# Sheet2.net
KiCad netlist of a schematic drawn in Altium Designer
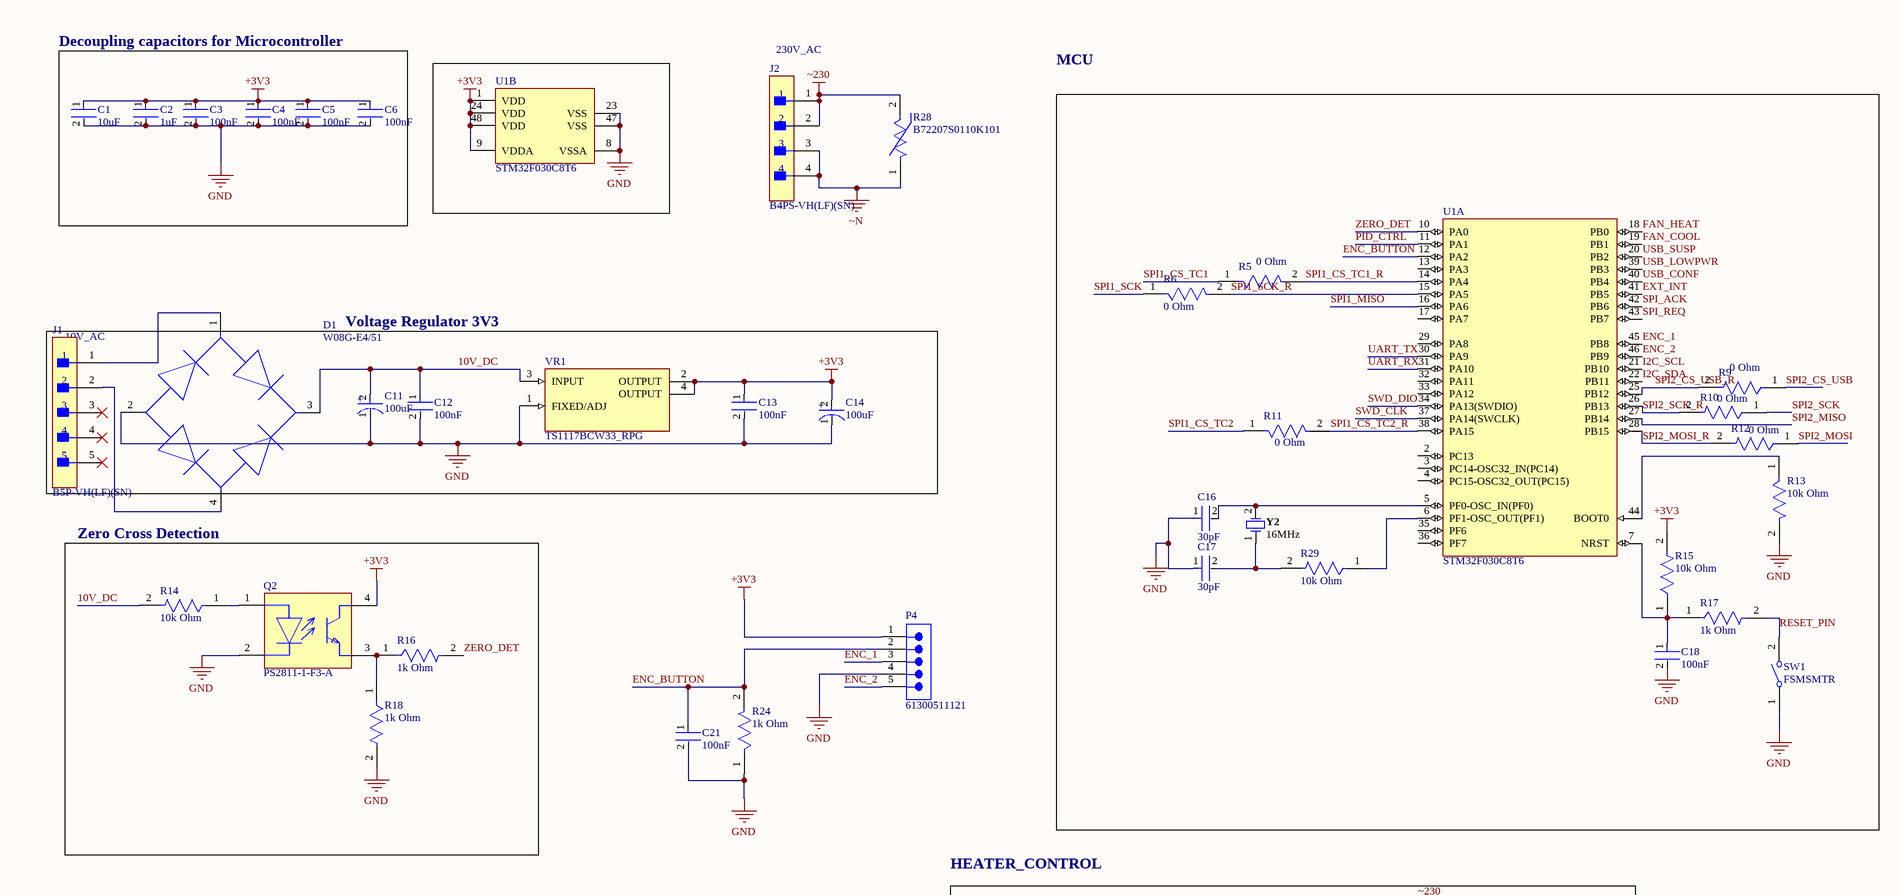
[diagram p0: Sheet2.SchDoc, top left]
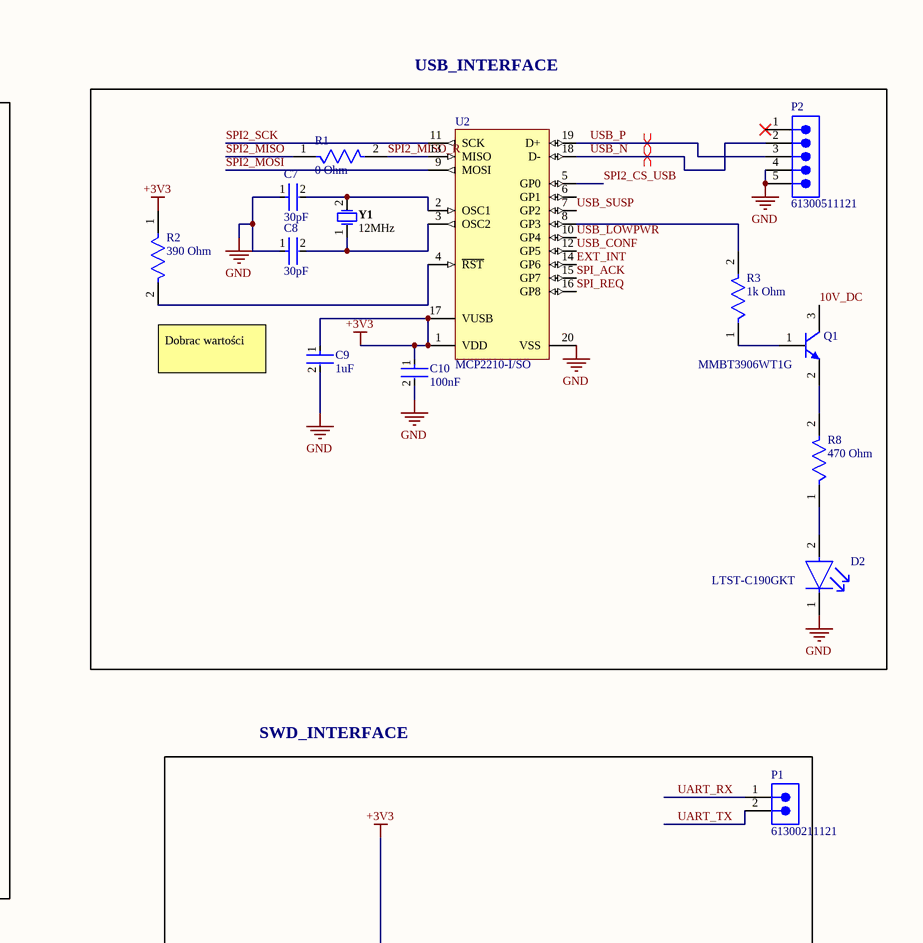
[diagram p1: Sheet2.SchDoc, top right]
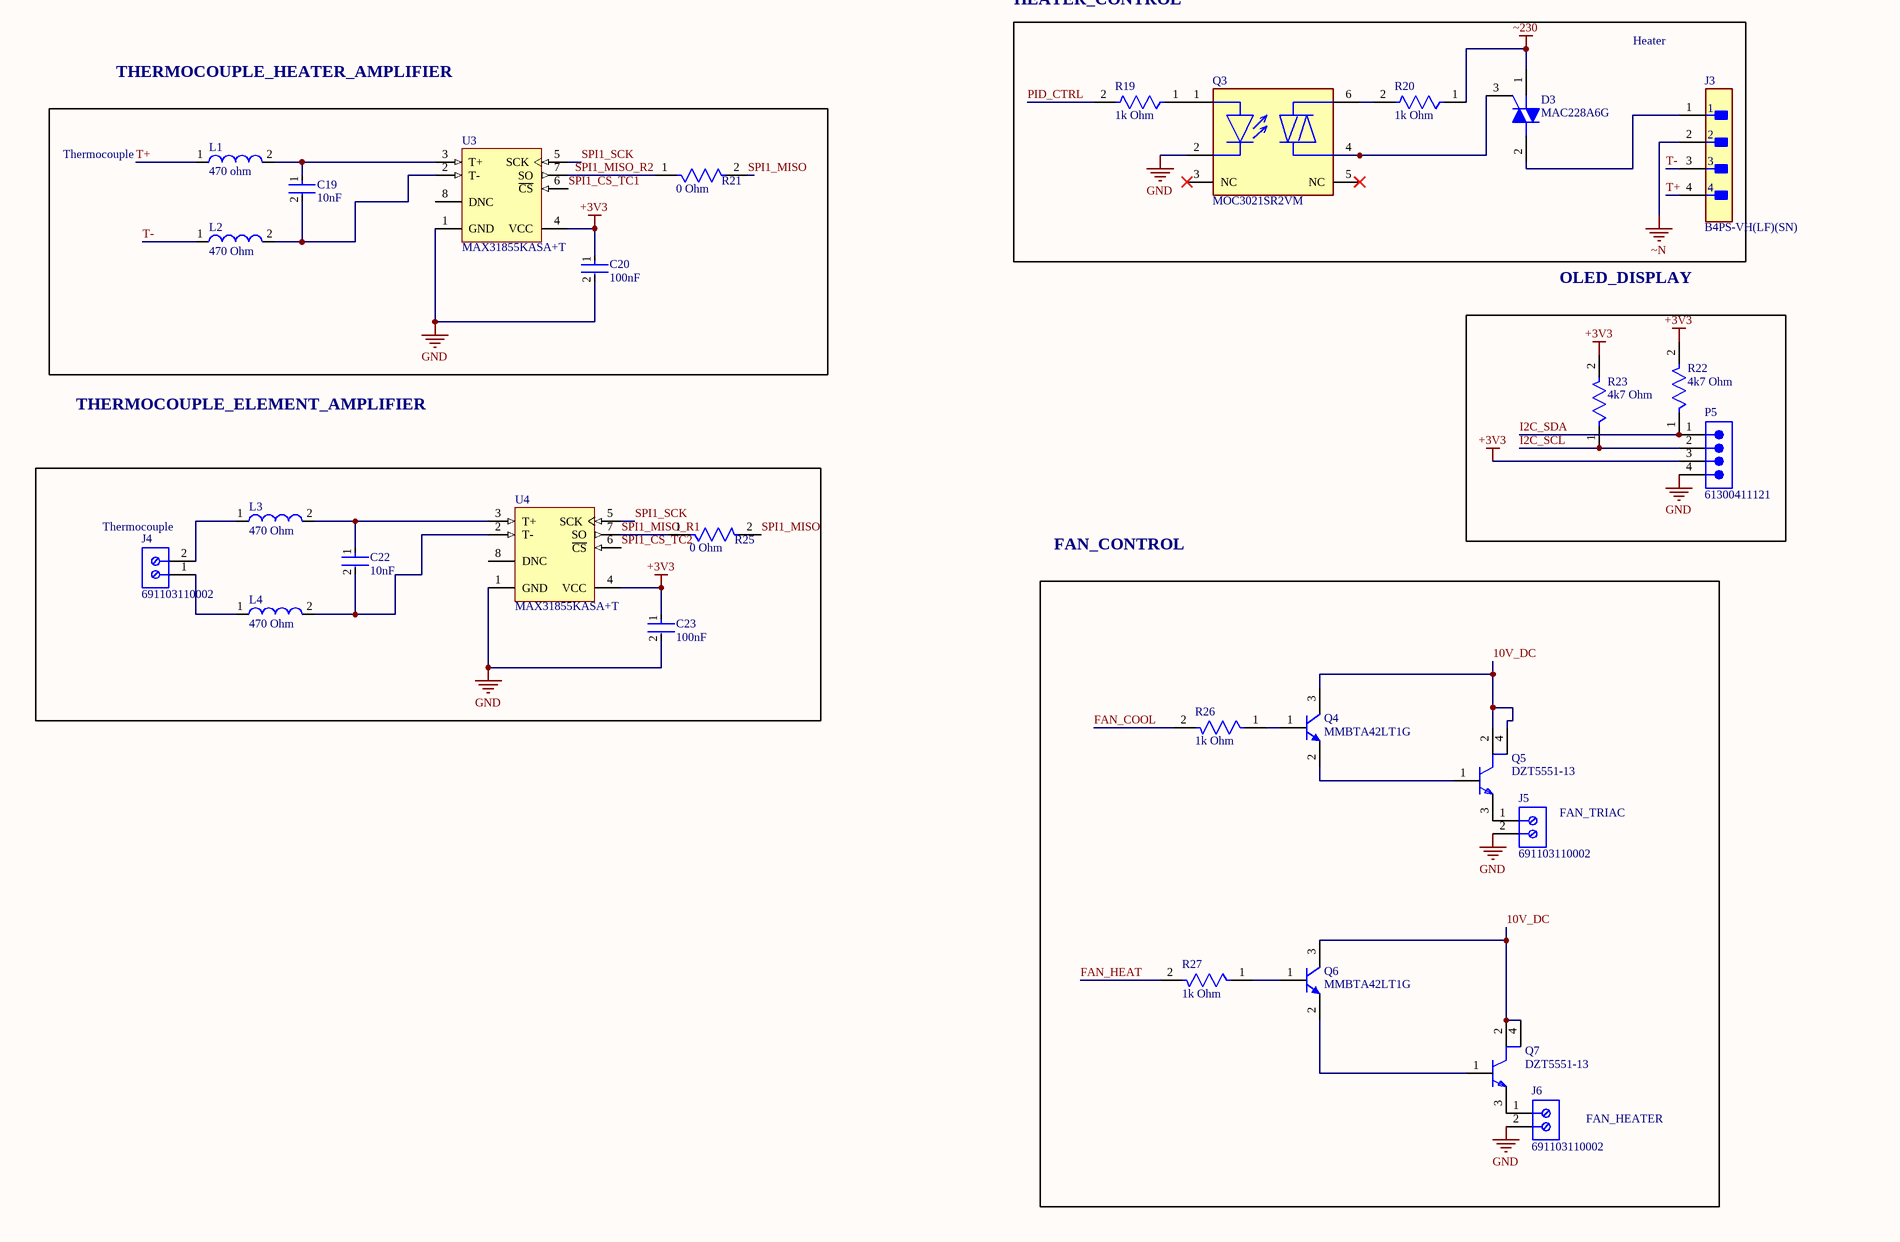
[diagram p2: Sheet2.SchDoc, bottom left]
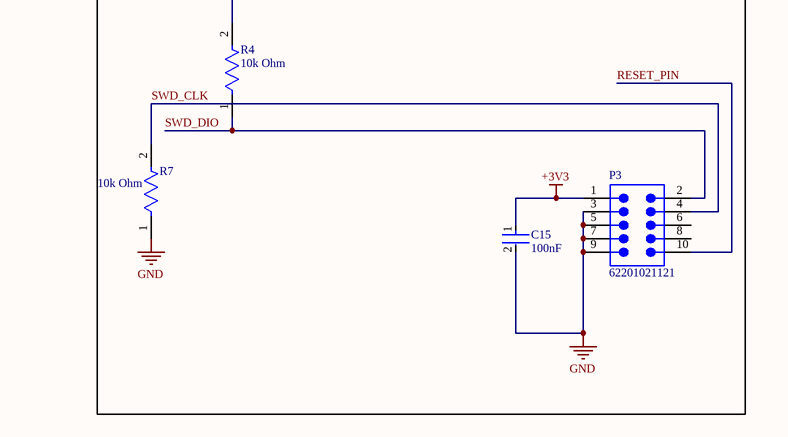
[diagram p3: Sheet2.SchDoc, bottom right]

(export (version "E")
  (design (tool "Eeschema 10.0.6"))
  (components
    (comp (ref "C1")
      (value "10uF")
      (footprint "FP-CC0805-0_85-MFG")
      (description "CAP CER 0.1UF 50V X7R 0805")
      (fields (field (name "TOLERANCE") "0.1") (field (name "MANUFACTURER PART NUMBER") "CC0805KRX7R9BB104"))
      (libsource (lib "Altium Content Vault") (part "11868f565c42a9108669ba33697ecf6"))
    )
    (comp (ref "C2")
      (value "1uF")
      (footprint "FP-CC0805-0_85-MFG")
      (description "CAP CER 0.1UF 50V X7R 0805")
      (fields (field (name "TOLERANCE") "0.1") (field (name "MANUFACTURER PART NUMBER") "CC0805KRX7R9BB104"))
      (libsource (lib "Altium Content Vault") (part "11868f565c42a9108669ba33697ecf6"))
    )
    (comp (ref "C3")
      (value "100nF")
      (footprint "FP-CC0805-0_85-MFG")
      (description "CAP CER 0.1UF 50V X7R 0805")
      (fields (field (name "TOLERANCE") "0.1") (field (name "MANUFACTURER PART NUMBER") "CC0805KRX7R9BB104"))
      (libsource (lib "Altium Content Vault") (part "11868f565c42a9108669ba33697ecf6"))
    )
    (comp (ref "C4")
      (value "100nF")
      (footprint "FP-CC0805-0_85-MFG")
      (description "CAP CER 0.1UF 50V X7R 0805")
      (fields (field (name "TOLERANCE") "0.1") (field (name "MANUFACTURER PART NUMBER") "CC0805KRX7R9BB104"))
      (libsource (lib "Altium Content Vault") (part "11868f565c42a9108669ba33697ecf6"))
    )
    (comp (ref "C5")
      (value "100nF")
      (footprint "FP-CC0805-0_85-MFG")
      (description "CAP CER 0.1UF 50V X7R 0805")
      (fields (field (name "TOLERANCE") "0.1") (field (name "MANUFACTURER PART NUMBER") "CC0805KRX7R9BB104"))
      (libsource (lib "Altium Content Vault") (part "11868f565c42a9108669ba33697ecf6"))
    )
    (comp (ref "C6")
      (value "100nF")
      (footprint "FP-CC0805-0_85-MFG")
      (description "CAP CER 0.1UF 50V X7R 0805")
      (fields (field (name "TOLERANCE") "0.1") (field (name "MANUFACTURER PART NUMBER") "CC0805KRX7R9BB104"))
      (libsource (lib "Altium Content Vault") (part "11868f565c42a9108669ba33697ecf6"))
    )
    (comp (ref "C7")
      (value "30pF")
      (footprint "FP-CC0805-0_85-MFG")
      (description "CAP CER 0.1UF 50V X7R 0805")
      (fields (field (name "TOLERANCE") "0.1") (field (name "MANUFACTURER PART NUMBER") "CC0805KRX7R9BB104"))
      (libsource (lib "Altium Content Vault") (part "11868f565c42a9108669ba33697ecf6"))
    )
    (comp (ref "C8")
      (value "30pF")
      (footprint "FP-CC0805-0_85-MFG")
      (description "CAP CER 0.1UF 50V X7R 0805")
      (fields (field (name "TOLERANCE") "0.1") (field (name "MANUFACTURER PART NUMBER") "CC0805KRX7R9BB104"))
      (libsource (lib "Altium Content Vault") (part "11868f565c42a9108669ba33697ecf6"))
    )
    (comp (ref "C9")
      (value "1uF")
      (footprint "FP-CC0805-0_85-MFG")
      (description "CAP CER 0.1UF 50V X7R 0805")
      (fields (field (name "TOLERANCE") "0.1") (field (name "MANUFACTURER PART NUMBER") "CC0805KRX7R9BB104"))
      (libsource (lib "Altium Content Vault") (part "11868f565c42a9108669ba33697ecf6"))
    )
    (comp (ref "C10")
      (value "100nF")
      (footprint "FP-CC0805-0_85-MFG")
      (description "CAP CER 0.1UF 50V X7R 0805")
      (fields (field (name "TOLERANCE") "0.1") (field (name "MANUFACTURER PART NUMBER") "CC0805KRX7R9BB104"))
      (libsource (lib "Altium Content Vault") (part "11868f565c42a9108669ba33697ecf6"))
    )
    (comp (ref "C11")
      (value "100uF")
      (footprint "FP-RAD-TH-D_10_0_5-L_12_5-MFG")
      (description "Aluminum Electrolytic Capacitors (Radial Lead Type) 3.3uF ±20% 400V")
      (fields (field (name "TOLERANCE") "20%") (field (name "VOLTAGE") "400V"))
      (libsource (lib "Altium Content Vault") (part "203bc49f2ac43e59fd269a8c329ed05"))
    )
    (comp (ref "C12")
      (value "100nF")
      (footprint "FP-CC0805-0_85-MFG")
      (description "CAP CER 0.1UF 50V X7R 0805")
      (fields (field (name "TOLERANCE") "0.1") (field (name "MANUFACTURER PART NUMBER") "CC0805KRX7R9BB104"))
      (libsource (lib "Altium Content Vault") (part "11868f565c42a9108669ba33697ecf6"))
    )
    (comp (ref "C13")
      (value "100nF")
      (footprint "FP-CC0805-0_85-MFG")
      (description "CAP CER 0.1UF 50V X7R 0805")
      (fields (field (name "TOLERANCE") "0.1") (field (name "MANUFACTURER PART NUMBER") "CC0805KRX7R9BB104"))
      (libsource (lib "Altium Content Vault") (part "11868f565c42a9108669ba33697ecf6"))
    )
    (comp (ref "C14")
      (value "100uF")
      (footprint "FP-RAD-TH-D_10_0_5-L_12_5-MFG")
      (description "Aluminum Electrolytic Capacitors (Radial Lead Type) 3.3uF ±20% 400V")
      (fields (field (name "TOLERANCE") "20%") (field (name "VOLTAGE") "400V"))
      (libsource (lib "Altium Content Vault") (part "203bc49f2ac43e59fd269a8c329ed05"))
    )
    (comp (ref "C15")
      (value "100nF")
      (footprint "FP-CC0805-0_85-MFG")
      (description "CAP CER 0.1UF 50V X7R 0805")
      (fields (field (name "TOLERANCE") "0.1") (field (name "MANUFACTURER PART NUMBER") "CC0805KRX7R9BB104"))
      (libsource (lib "Altium Content Vault") (part "11868f565c42a9108669ba33697ecf6"))
    )
    (comp (ref "C16")
      (value "30pF")
      (footprint "FP-CC0805-0_85-MFG")
      (description "CAP CER 0.1UF 50V X7R 0805")
      (fields (field (name "TOLERANCE") "0.1") (field (name "MANUFACTURER PART NUMBER") "CC0805KRX7R9BB104"))
      (libsource (lib "Altium Content Vault") (part "11868f565c42a9108669ba33697ecf6"))
    )
    (comp (ref "C17")
      (value "30pF")
      (footprint "FP-CC0805-0_85-MFG")
      (description "CAP CER 0.1UF 50V X7R 0805")
      (fields (field (name "TOLERANCE") "0.1") (field (name "MANUFACTURER PART NUMBER") "CC0805KRX7R9BB104"))
      (libsource (lib "Altium Content Vault") (part "11868f565c42a9108669ba33697ecf6"))
    )
    (comp (ref "C18")
      (value "100nF")
      (footprint "FP-CC0805-0_85-MFG")
      (description "CAP CER 0.1UF 50V X7R 0805")
      (fields (field (name "TOLERANCE") "0.1") (field (name "MANUFACTURER PART NUMBER") "CC0805KRX7R9BB104"))
      (libsource (lib "Altium Content Vault") (part "11868f565c42a9108669ba33697ecf6"))
    )
    (comp (ref "C19")
      (value "10nF")
      (footprint "FP-CC0805-0_85-MFG")
      (description "CAP CER 0.1UF 50V X7R 0805")
      (fields (field (name "TOLERANCE") "0.1") (field (name "MANUFACTURER PART NUMBER") "CC0805KRX7R9BB104"))
      (libsource (lib "Altium Content Vault") (part "11868f565c42a9108669ba33697ecf6"))
    )
    (comp (ref "C20")
      (value "100nF")
      (footprint "FP-CC0805-0_85-MFG")
      (description "CAP CER 0.1UF 50V X7R 0805")
      (fields (field (name "TOLERANCE") "0.1") (field (name "MANUFACTURER PART NUMBER") "CC0805KRX7R9BB104"))
      (libsource (lib "Altium Content Vault") (part "11868f565c42a9108669ba33697ecf6"))
    )
    (comp (ref "C21")
      (value "100nF")
      (footprint "FP-CC0805-0_85-MFG")
      (description "CAP CER 0.1UF 50V X7R 0805")
      (fields (field (name "TOLERANCE") "0.1") (field (name "MANUFACTURER PART NUMBER") "CC0805KRX7R9BB104"))
      (libsource (lib "Altium Content Vault") (part "11868f565c42a9108669ba33697ecf6"))
    )
    (comp (ref "C22")
      (value "10nF")
      (footprint "FP-CC0805-0_85-MFG")
      (description "CAP CER 0.1UF 50V X7R 0805")
      (fields (field (name "TOLERANCE") "0.1") (field (name "MANUFACTURER PART NUMBER") "CC0805KRX7R9BB104"))
      (libsource (lib "Altium Content Vault") (part "11868f565c42a9108669ba33697ecf6"))
    )
    (comp (ref "C23")
      (value "100nF")
      (footprint "FP-CC0805-0_85-MFG")
      (description "CAP CER 0.1UF 50V X7R 0805")
      (fields (field (name "TOLERANCE") "0.1") (field (name "MANUFACTURER PART NUMBER") "CC0805KRX7R9BB104"))
      (libsource (lib "Altium Content Vault") (part "11868f565c42a9108669ba33697ecf6"))
    )
    (comp (ref "D1")
      (value "W08G-E4/51")
      (footprint "FP-WOG-MFG")
      (description "W08G-E4/51 Diode Rectifier Bridge Single 800V 1.5A 4-Pin Case WOG Bulk")
      (libsource (lib "Altium Content Vault") (part "7f679ecdc54638986ed3433d0c5b104"))
    )
    (comp (ref "D2")
      (value "LTST-C190GKT")
      (footprint "FP-LTST-C190GKT-MFG")
      (description "LED GREEN CLEAR CHIP SMD")
      (fields (field (name "VOLTAGE") "2V"))
      (libsource (lib "Altium Content Vault") (part "8706943c75ba83719d021d2fdc84c58"))
    )
    (comp (ref "D3")
      (value "MAC228A6G")
      (footprint "ONSC-TO-220-3-221A-09")
      (description "Sensitive Gate Triacs, Silicon Bidirectional Thyristor, 3-Pin TO-220, Pb-Free, Bulk Box")
      (fields (field (name "MANUFACTURER") "On Semiconductor"))
      (libsource (lib "Altium Content Vault") (part "ONSC-TRIAC-MT1MT2G-3"))
    )
    (comp (ref "J1")
      (value "B5P-VH(LF)(SN)")
      (footprint "FP-B5P-VH_LF_SN-MFG")
      (description "CONN HEADER VERT 5POS 3.96MM")
      (libsource (lib "Altium Content Vault") (part "051ac7c1f60a91215dd69c4e70fad1a"))
    )
    (comp (ref "J2")
      (value "B4PS-VH(LF)(SN)")
      (footprint "FP-B4PS-VH_LF_SN-MFG")
      (description "CONN HEADER R/A 4POS 3.96MM")
      (libsource (lib "Altium Content Vault") (part "299a8cea1bdcbc3624fe62c390fa72c"))
    )
    (comp (ref "J3")
      (value "B4PS-VH(LF)(SN)")
      (footprint "FP-B4PS-VH_LF_SN-MFG")
      (description "CONN HEADER R/A 4POS 3.96MM")
      (libsource (lib "") (part "299a8cea1bdcbc3624fe62c390fa72c_1"))
    )
    (comp (ref "J4")
      (value "691103110002")
      (footprint "691103110002")
      (fields (field (name "VOLTAGE") "125V"))
      (libsource (lib "Altium Content Vault") (part "TBL - 1R - 02P - Screw"))
    )
    (comp (ref "J5")
      (value "691103110002")
      (footprint "691103110002")
      (fields (field (name "VOLTAGE") "125V"))
      (libsource (lib "Altium Content Vault") (part "TBL - 1R - 02P - Screw"))
    )
    (comp (ref "J6")
      (value "691103110002")
      (footprint "691103110002")
      (fields (field (name "VOLTAGE") "125V"))
      (libsource (lib "Altium Content Vault") (part "TBL - 1R - 02P - Screw"))
    )
    (comp (ref "L1")
      (value "470 ohm")
      (footprint "SMD-0805")
      (description "SMD EMI Suppression Ferrite Bead WE-CBF, Z = 470 Ohm")
      (libsource (lib "Altium Content Vault") (part "PAS-IND-INDUCTOR-2"))
    )
    (comp (ref "L2")
      (value "470 Ohm")
      (footprint "SMD-0805")
      (description "SMD EMI Suppression Ferrite Bead WE-CBF, Z = 470 Ohm")
      (libsource (lib "Altium Content Vault") (part "PAS-IND-INDUCTOR-2"))
    )
    (comp (ref "L3")
      (value "470 Ohm")
      (footprint "SMD-0805")
      (description "SMD EMI Suppression Ferrite Bead WE-CBF, Z = 470 Ohm")
      (libsource (lib "Altium Content Vault") (part "PAS-IND-INDUCTOR-2"))
    )
    (comp (ref "L4")
      (value "470 Ohm")
      (footprint "SMD-0805")
      (description "SMD EMI Suppression Ferrite Bead WE-CBF, Z = 470 Ohm")
      (libsource (lib "Altium Content Vault") (part "PAS-IND-INDUCTOR-2"))
    )
    (comp (ref "P1")
      (value "61300211121")
      (footprint "61300211121")
      (libsource (lib "Altium Content Vault") (part "Header_Male_1R_02P"))
    )
    (comp (ref "P2")
      (value "61300511121")
      (footprint "61300511121")
      (libsource (lib "Altium Content Vault") (part "Header_Male_1R_05P"))
    )
    (comp (ref "P3")
      (value "62201021121")
      (footprint "62201021121")
      (libsource (lib "Altium Content Vault") (part "Header_Male_2R_10P"))
    )
    (comp (ref "P4")
      (value "61300511121")
      (footprint "61300511121")
      (libsource (lib "Altium Content Vault") (part "Header_Male_1R_05P"))
    )
    (comp (ref "P5")
      (value "61300411121")
      (footprint "61300411121")
      (libsource (lib "Altium Content Vault") (part "Header_Male_1R_04P"))
    )
    (comp (ref "Q1")
      (value "MMBT3906WT1G")
      (footprint "ONSC-SC-70-3-419-04_V")
      (description "General Purpose Transistor, PNP Silicon, 3-Pin SC70, Pb-Free, Tape and Reel")
      (fields (field (name "MANUFACTURER") "On Semiconductor"))
      (libsource (lib "Altium Content Vault") (part "ONSC-NPN-B1E2C3-3"))
    )
    (comp (ref "Q2")
      (value "PS2811-1-F3-A")
      (footprint "SOP127P700X210_HS-5_SO4-Opto2_N")
      (description "Optocoupler DC-IN 1-CH Transistor DC-OUT 4-Pin SSOP Embossed T/R")
      (libsource (lib "Altium Content Vault") (part "f4732c5a005c16655bf03302f8bd1cc"))
    )
    (comp (ref "Q3")
      (value "MOC3021SR2VM")
      (footprint "FP-646BY-MFG")
      (description "MOC3021SR2VM Triac Driver Output Optocoupler, 6-Pin DIP 400V Random Phase")
      (libsource (lib "Altium Content Vault") (part "315d33d7a3de83856d3bd334bf87c2f"))
    )
    (comp (ref "Q4")
      (value "MMBTA42LT1G")
      (footprint "ONSC-SOT-23-3-318-08_V")
      (description "High Voltage Transistor, NPN Silicon, 3-Pin SOT-23, Pb-Free, Tape and Reel")
      (fields (field (name "MANUFACTURER") "On Semiconductor"))
      (libsource (lib "Altium Content Vault") (part "ONSC-NPN-B1E2C3-3"))
    )
    (comp (ref "Q5")
      (value "DZT5551-13")
      (footprint "FP-SOT223-MFG")
      (description "TRANS NPN 160V 0.6A SOT-223")
      (fields
        (field (name "MANUFACTURER") "Diodes")
        (field (name "OCTOPART") "https://octopart.com/dzt5551-13-diodes+inc.-12426785")
      )
      (libsource (lib "Altium Content Vault") (part "ef0222921274e2dfe3c88fb5f98777d"))
    )
    (comp (ref "Q6")
      (value "MMBTA42LT1G")
      (footprint "ONSC-SOT-23-3-318-08_V")
      (description "High Voltage Transistor, NPN Silicon, 3-Pin SOT-23, Pb-Free, Tape and Reel")
      (fields (field (name "MANUFACTURER") "On Semiconductor"))
      (libsource (lib "Altium Content Vault") (part "ONSC-NPN-B1E2C3-3"))
    )
    (comp (ref "Q7")
      (value "DZT5551-13")
      (footprint "FP-SOT223-MFG")
      (description "TRANS NPN 160V 0.6A SOT-223")
      (fields
        (field (name "MANUFACTURER") "Diodes")
        (field (name "OCTOPART") "https://octopart.com/dzt5551-13-diodes+inc.-12426785")
      )
      (libsource (lib "Altium Content Vault") (part "ef0222921274e2dfe3c88fb5f98777d"))
    )
    (comp (ref "R1")
      (value "0 Ohm")
      (footprint "FP-RMCF0805-MFG")
      (description "RES 0 OHM JUMPER 1/8W 0805")
      (libsource (lib "Altium Content Vault") (part "1029c3af85768c4190bb7ad29bc67b5"))
    )
    (comp (ref "R2")
      (value "390 Ohm")
      (footprint "FP-RMCF0805-MFG")
      (description "RES 0 OHM JUMPER 1/8W 0805")
      (libsource (lib "Altium Content Vault") (part "1029c3af85768c4190bb7ad29bc67b5"))
    )
    (comp (ref "R3")
      (value "1k Ohm")
      (footprint "FP-RMCF0805-MFG")
      (description "RES 0 OHM JUMPER 1/8W 0805")
      (libsource (lib "Altium Content Vault") (part "1029c3af85768c4190bb7ad29bc67b5"))
    )
    (comp (ref "R4")
      (value "10k Ohm")
      (footprint "FP-RMCF0805-MFG")
      (description "RES 0 OHM JUMPER 1/8W 0805")
      (libsource (lib "Altium Content Vault") (part "1029c3af85768c4190bb7ad29bc67b5"))
    )
    (comp (ref "R5")
      (value "0 Ohm")
      (footprint "FP-RMCF0805-MFG")
      (description "RES 0 OHM JUMPER 1/8W 0805")
      (libsource (lib "Altium Content Vault") (part "1029c3af85768c4190bb7ad29bc67b5"))
    )
    (comp (ref "R6")
      (value "0 Ohm")
      (footprint "FP-RMCF0805-MFG")
      (description "RES 0 OHM JUMPER 1/8W 0805")
      (libsource (lib "Altium Content Vault") (part "1029c3af85768c4190bb7ad29bc67b5"))
    )
    (comp (ref "R7")
      (value "10k Ohm")
      (footprint "FP-RMCF0805-MFG")
      (description "RES 0 OHM JUMPER 1/8W 0805")
      (libsource (lib "Altium Content Vault") (part "1029c3af85768c4190bb7ad29bc67b5"))
    )
    (comp (ref "R8")
      (value "470 Ohm")
      (footprint "FP-RMCF0805-MFG")
      (description "RES 0 OHM JUMPER 1/8W 0805")
      (libsource (lib "Altium Content Vault") (part "1029c3af85768c4190bb7ad29bc67b5"))
    )
    (comp (ref "R9")
      (value "0 Ohm")
      (footprint "FP-RMCF0805-MFG")
      (description "RES 0 OHM JUMPER 1/8W 0805")
      (libsource (lib "Altium Content Vault") (part "1029c3af85768c4190bb7ad29bc67b5"))
    )
    (comp (ref "R10")
      (value "0 Ohm")
      (footprint "FP-RMCF0805-MFG")
      (description "RES 0 OHM JUMPER 1/8W 0805")
      (libsource (lib "Altium Content Vault") (part "1029c3af85768c4190bb7ad29bc67b5"))
    )
    (comp (ref "R11")
      (value "0 Ohm")
      (footprint "FP-RMCF0805-MFG")
      (description "RES 0 OHM JUMPER 1/8W 0805")
      (libsource (lib "Altium Content Vault") (part "1029c3af85768c4190bb7ad29bc67b5"))
    )
    (comp (ref "R12")
      (value "0 Ohm")
      (footprint "FP-RMCF0805-MFG")
      (description "RES 0 OHM JUMPER 1/8W 0805")
      (libsource (lib "Altium Content Vault") (part "1029c3af85768c4190bb7ad29bc67b5"))
    )
    (comp (ref "R13")
      (value "10k Ohm")
      (footprint "FP-RMCF0805-MFG")
      (description "RES 0 OHM JUMPER 1/8W 0805")
      (libsource (lib "Altium Content Vault") (part "1029c3af85768c4190bb7ad29bc67b5"))
    )
    (comp (ref "R14")
      (value "10k Ohm")
      (footprint "FP-RMCF0805-MFG")
      (description "RES 0 OHM JUMPER 1/8W 0805")
      (libsource (lib "Altium Content Vault") (part "1029c3af85768c4190bb7ad29bc67b5"))
    )
    (comp (ref "R15")
      (value "10k Ohm")
      (footprint "FP-RMCF0805-MFG")
      (description "RES 0 OHM JUMPER 1/8W 0805")
      (libsource (lib "Altium Content Vault") (part "1029c3af85768c4190bb7ad29bc67b5"))
    )
    (comp (ref "R16")
      (value "1k Ohm")
      (footprint "FP-RMCF0805-MFG")
      (description "RES 0 OHM JUMPER 1/8W 0805")
      (libsource (lib "Altium Content Vault") (part "1029c3af85768c4190bb7ad29bc67b5"))
    )
    (comp (ref "R17")
      (value "1k Ohm")
      (footprint "FP-RMCF0805-MFG")
      (description "RES 0 OHM JUMPER 1/8W 0805")
      (libsource (lib "Altium Content Vault") (part "1029c3af85768c4190bb7ad29bc67b5"))
    )
    (comp (ref "R18")
      (value "1k Ohm")
      (footprint "FP-RMCF0805-MFG")
      (description "RES 0 OHM JUMPER 1/8W 0805")
      (libsource (lib "Altium Content Vault") (part "1029c3af85768c4190bb7ad29bc67b5"))
    )
    (comp (ref "R19")
      (value "1k Ohm")
      (footprint "FP-RMCF0805-MFG")
      (description "RES 0 OHM JUMPER 1/8W 0805")
      (libsource (lib "Altium Content Vault") (part "1029c3af85768c4190bb7ad29bc67b5"))
    )
    (comp (ref "R20")
      (value "1k Ohm")
      (footprint "FP-RMCF0805-MFG")
      (description "RES 0 OHM JUMPER 1/8W 0805")
      (libsource (lib "Altium Content Vault") (part "1029c3af85768c4190bb7ad29bc67b5"))
    )
    (comp (ref "R21")
      (value "0 Ohm")
      (footprint "FP-RMCF0805-MFG")
      (description "RES 0 OHM JUMPER 1/8W 0805")
      (libsource (lib "Altium Content Vault") (part "1029c3af85768c4190bb7ad29bc67b5"))
    )
    (comp (ref "R22")
      (value "4k7 Ohm")
      (footprint "FP-RMCF0805-MFG")
      (description "RES 0 OHM JUMPER 1/8W 0805")
      (libsource (lib "Altium Content Vault") (part "1029c3af85768c4190bb7ad29bc67b5"))
    )
    (comp (ref "R23")
      (value "4k7 Ohm")
      (footprint "FP-RMCF0805-MFG")
      (description "RES 0 OHM JUMPER 1/8W 0805")
      (libsource (lib "Altium Content Vault") (part "1029c3af85768c4190bb7ad29bc67b5"))
    )
    (comp (ref "R24")
      (value "1k Ohm")
      (footprint "FP-RMCF0805-MFG")
      (description "RES 0 OHM JUMPER 1/8W 0805")
      (libsource (lib "Altium Content Vault") (part "1029c3af85768c4190bb7ad29bc67b5"))
    )
    (comp (ref "R25")
      (value "0 Ohm")
      (footprint "FP-RMCF0805-MFG")
      (description "RES 0 OHM JUMPER 1/8W 0805")
      (libsource (lib "Altium Content Vault") (part "1029c3af85768c4190bb7ad29bc67b5"))
    )
    (comp (ref "R26")
      (value "1k Ohm")
      (footprint "FP-RMCF0805-MFG")
      (description "RES 0 OHM JUMPER 1/8W 0805")
      (libsource (lib "Altium Content Vault") (part "1029c3af85768c4190bb7ad29bc67b5"))
    )
    (comp (ref "R27")
      (value "1k Ohm")
      (footprint "FP-RMCF0805-MFG")
      (description "RES 0 OHM JUMPER 1/8W 0805")
      (libsource (lib "Altium Content Vault") (part "1029c3af85768c4190bb7ad29bc67b5"))
    )
    (comp (ref "R28")
      (value "B72207S0110K101")
      (footprint "FP-B72207S0110K101-MFG")
      (description "VARISTOR 18V 250A DISC 7MM")
      (fields
        (field (name "MANUFACTURER") "EPCOS")
        (field (name "OCTOPART") "https://octopart.com/b72207s0110k101-epcos-11931358")
      )
      (libsource (lib "Altium Content Vault") (part "78a88060d5b7b043d6e48adc4284376"))
    )
    (comp (ref "R29")
      (value "10k Ohm")
      (footprint "FP-RMCF0805-MFG")
      (description "RES 0 OHM JUMPER 1/8W 0805")
      (libsource (lib "Altium Content Vault") (part "1029c3af85768c4190bb7ad29bc67b5"))
    )
    (comp (ref "SW1")
      (value "FSMSMTR")
      (footprint "TECO-FSMSMTR_V")
      (description "FSMSM Push Button Switch, 50 mA, -35 to 85 degC, 2-Pin SMD, RoHS, Tape and Reel")
      (fields (field (name "MANUFACTURER") "TE Connectivity"))
      (libsource (lib "Altium Content Vault") (part "SW-SPST-2_C"))
    )
    (comp (ref "U1")
      (value "STM32F030C8T6")
      (footprint "STM-LQFP48_M")
      (libsource (lib "Altium Content Vault") (part "MC-ARM-STM32F030_X8-SQ48"))
    )
    (comp (ref "U2")
      (value "MCP2210-I/SO")
      (footprint "SOIC-SO20_N")
      (description "USB-to-SPI Protocol Converter with GPIO (Master Mode), 20-Pin SOIC, Industrial Temperature")
      (libsource (lib "Altium Content Vault") (part "COM-USB-MCP2210-20"))
    )
    (comp (ref "U3")
      (value "MAX31855KASA+T")
      (footprint "MAXM-S8+4_N")
      (fields (field (name "GENERIC PART NUMBER") "MAX31855"))
      (libsource (lib "Altium Content Vault") (part "MAX31855-S8+4"))
    )
    (comp (ref "U4")
      (value "MAX31855KASA+T")
      (footprint "MAXM-S8+4_N")
      (fields (field (name "GENERIC PART NUMBER") "MAX31855"))
      (libsource (lib "Altium Content Vault") (part "MAX31855-S8+4"))
    )
    (comp (ref "VR1")
      (value "TS1117BCW33_RPG")
      (footprint "VREG_TS1117BCW50_RPG")
      (fields (field (name "MP") "TS1117BCW50_RPG"))
      (libsource (lib "TS1117BCW50_RPG") (part "TS1117BCW50_RPG"))
    )
    (comp (ref "Y1")
      (value "12MHz")
      (footprint "FOX-FOXSLF160-20")
      (description "Resistance Weld Thru-Hole Crystal, 16 MHz, -20 to 70 degC, 2-Pin THD, RoHS, Bulk")
      (fields (field (name "TOLERANCE") "1%"))
      (libsource (lib "Altium Content Vault") (part "XTAL-1-2-2"))
    )
    (comp (ref "Y2")
      (value "16MHz")
      (footprint "FOX-FOXSLF160-20")
      (description "Resistance Weld Thru-Hole Crystal, 16 MHz, -20 to 70 degC, 2-Pin THD, RoHS, Bulk")
      (fields (field (name "TOLERANCE") "1%"))
      (libsource (lib "Altium Content Vault") (part "XTAL-1-2-2"))
    )
  )
  (nets
    (net (code "1") (name "+3V3") (class "Default")
      (node (ref "C1") (pin "1") (pinfunction "1_1") (pintype "passive"))
      (node (ref "C10") (pin "1") (pinfunction "1_1") (pintype "passive"))
      (node (ref "C13") (pin "1") (pinfunction "1_1") (pintype "passive"))
      (node (ref "C14") (pin "2") (pinfunction "A_2") (pintype "passive"))
      (node (ref "C15") (pin "1") (pinfunction "1_1") (pintype "passive"))
      (node (ref "C2") (pin "1") (pinfunction "1_1") (pintype "passive"))
      (node (ref "C20") (pin "1") (pinfunction "1_1") (pintype "passive"))
      (node (ref "C23") (pin "1") (pinfunction "1_1") (pintype "passive"))
      (node (ref "C3") (pin "1") (pinfunction "1_1") (pintype "passive"))
      (node (ref "C4") (pin "1") (pinfunction "1_1") (pintype "passive"))
      (node (ref "C5") (pin "1") (pinfunction "1_1") (pintype "passive"))
      (node (ref "C6") (pin "1") (pinfunction "1_1") (pintype "passive"))
      (node (ref "C9") (pin "1") (pinfunction "1_1") (pintype "passive"))
      (node (ref "P3") (pin "1") (pinfunction "1_1") (pintype "passive"))
      (node (ref "P4") (pin "1") (pinfunction "1_1") (pintype "passive"))
      (node (ref "P5") (pin "3") (pinfunction "3_3") (pintype "passive"))
      (node (ref "Q2") (pin "4") (pinfunction "C_4") (pintype "passive"))
      (node (ref "R15") (pin "2") (pinfunction "2_2") (pintype "passive"))
      (node (ref "R2") (pin "1") (pinfunction "1_1") (pintype "passive"))
      (node (ref "R22") (pin "2") (pinfunction "2_2") (pintype "passive"))
      (node (ref "R23") (pin "2") (pinfunction "2_2") (pintype "passive"))
      (node (ref "R4") (pin "2") (pinfunction "2_2") (pintype "passive"))
      (node (ref "U1") (pin "1") (pinfunction "VDD_1") (pintype "power_in"))
      (node (ref "U1") (pin "24") (pinfunction "VDD_24") (pintype "power_in"))
      (node (ref "U1") (pin "48") (pinfunction "VDD_48") (pintype "power_in"))
      (node (ref "U1") (pin "9") (pinfunction "VDDA_9") (pintype "power_in"))
      (node (ref "U2") (pin "1") (pinfunction "VDD_1") (pintype "power_in"))
      (node (ref "U2") (pin "17") (pinfunction "VUSB_17") (pintype "power_in"))
      (node (ref "U3") (pin "4") (pinfunction "VCC_4") (pintype "power_in"))
      (node (ref "U4") (pin "4") (pinfunction "VCC_4") (pintype "power_in"))
      (node (ref "VR1") (pin "2") (pinfunction "OUTPUT_2") (pintype "power_in"))
      (node (ref "VR1") (pin "4") (pinfunction "OUTPUT_4") (pintype "power_in"))
    )
    (net (code "2") (name "/10V_DC") (class "Default")
      (node (ref "C11") (pin "2") (pinfunction "A_2") (pintype "passive"))
      (node (ref "C12") (pin "1") (pinfunction "1_1") (pintype "passive"))
      (node (ref "D1") (pin "3") (pinfunction "-_3") (pintype "passive"))
      (node (ref "Q1") (pin "3") (pinfunction "C_3") (pintype "passive"))
      (node (ref "Q4") (pin "3") (pinfunction "C_3") (pintype "passive"))
      (node (ref "Q5") (pin "2") (pinfunction "C_2") (pintype "passive"))
      (node (ref "Q5") (pin "4") (pinfunction "C_4") (pintype "passive"))
      (node (ref "Q6") (pin "3") (pinfunction "C_3") (pintype "passive"))
      (node (ref "Q7") (pin "2") (pinfunction "C_2") (pintype "passive"))
      (node (ref "Q7") (pin "4") (pinfunction "C_4") (pintype "passive"))
      (node (ref "R14") (pin "2") (pinfunction "2_2") (pintype "passive"))
      (node (ref "VR1") (pin "3") (pinfunction "INPUT_3") (pintype "input"))
    )
    (net (code "3") (name "/ENC_1") (class "Default")
      (node (ref "P4") (pin "3") (pinfunction "3_3") (pintype "passive"))
      (node (ref "U1") (pin "45") (pinfunction "PB8_45") (pintype "bidirectional"))
    )
    (net (code "4") (name "/ENC_2") (class "Default")
      (node (ref "P4") (pin "5") (pinfunction "5_5") (pintype "passive"))
      (node (ref "U1") (pin "46") (pinfunction "PB9_46") (pintype "bidirectional"))
    )
    (net (code "5") (name "/ENC_BUTTON") (class "Default")
      (node (ref "C21") (pin "1") (pinfunction "1_1") (pintype "passive"))
      (node (ref "P4") (pin "2") (pinfunction "2_2") (pintype "passive"))
      (node (ref "R24") (pin "2") (pinfunction "2_2") (pintype "passive"))
      (node (ref "U1") (pin "12") (pinfunction "PA2_12") (pintype "bidirectional"))
    )
    (net (code "6") (name "/EXT_INT") (class "Default")
      (node (ref "U1") (pin "41") (pinfunction "PB5_41") (pintype "bidirectional"))
      (node (ref "U2") (pin "14") (pinfunction "GP6_14") (pintype "bidirectional"))
    )
    (net (code "7") (name "/FAN_COOL") (class "Default")
      (node (ref "R26") (pin "2") (pinfunction "2_2") (pintype "passive"))
      (node (ref "U1") (pin "19") (pinfunction "PB1_19") (pintype "bidirectional"))
    )
    (net (code "8") (name "/FAN_HEAT") (class "Default")
      (node (ref "R27") (pin "2") (pinfunction "2_2") (pintype "passive"))
      (node (ref "U1") (pin "18") (pinfunction "PB0_18") (pintype "bidirectional"))
    )
    (net (code "9") (name "/I2C_SCL") (class "Default")
      (node (ref "P5") (pin "2") (pinfunction "2_2") (pintype "passive"))
      (node (ref "R23") (pin "1") (pinfunction "1_1") (pintype "passive"))
      (node (ref "U1") (pin "21") (pinfunction "PB10_21") (pintype "bidirectional"))
    )
    (net (code "10") (name "/I2C_SDA") (class "Default")
      (node (ref "P5") (pin "1") (pinfunction "1_1") (pintype "passive"))
      (node (ref "R22") (pin "1") (pinfunction "1_1") (pintype "passive"))
      (node (ref "U1") (pin "22") (pinfunction "PB11_22") (pintype "bidirectional"))
    )
    (net (code "11") (name "/PID_CTRL") (class "Default")
      (node (ref "R19") (pin "2") (pinfunction "2_2") (pintype "passive"))
      (node (ref "U1") (pin "11") (pinfunction "PA1_11") (pintype "bidirectional"))
    )
    (net (code "12") (name "/RESET_PIN") (class "Default")
      (node (ref "P3") (pin "10") (pinfunction "10_10") (pintype "passive"))
      (node (ref "R17") (pin "2") (pinfunction "2_2") (pintype "passive"))
      (node (ref "SW1") (pin "2") (pinfunction "2_2") (pintype "passive"))
    )
    (net (code "13") (name "/SPI1_CS_TC1") (class "Default")
      (node (ref "R5") (pin "1") (pinfunction "1_1") (pintype "passive"))
      (node (ref "U3") (pin "6") (pinfunction "~{CS}_6") (pintype "input"))
    )
    (net (code "14") (name "/SPI1_CS_TC1_R") (class "Default")
      (node (ref "R5") (pin "2") (pinfunction "2_2") (pintype "passive"))
      (node (ref "U1") (pin "14") (pinfunction "PA4_14") (pintype "bidirectional"))
    )
    (net (code "15") (name "/SPI1_CS_TC2") (class "Default")
      (node (ref "R11") (pin "1") (pinfunction "1_1") (pintype "passive"))
      (node (ref "U4") (pin "6") (pinfunction "~{CS}_6") (pintype "input"))
    )
    (net (code "16") (name "/SPI1_CS_TC2_R") (class "Default")
      (node (ref "R11") (pin "2") (pinfunction "2_2") (pintype "passive"))
      (node (ref "U1") (pin "38") (pinfunction "PA15_38") (pintype "bidirectional"))
    )
    (net (code "17") (name "/SPI1_MISO") (class "Default")
      (node (ref "R21") (pin "2") (pinfunction "2_2") (pintype "passive"))
      (node (ref "R25") (pin "2") (pinfunction "2_2") (pintype "passive"))
      (node (ref "U1") (pin "16") (pinfunction "PA6_16") (pintype "bidirectional"))
    )
    (net (code "18") (name "/SPI1_MISO_R1") (class "Default")
      (node (ref "R25") (pin "1") (pinfunction "1_1") (pintype "passive"))
      (node (ref "U4") (pin "7") (pinfunction "SO_7") (pintype "output"))
    )
    (net (code "19") (name "/SPI1_MISO_R2") (class "Default")
      (node (ref "R21") (pin "1") (pinfunction "1_1") (pintype "passive"))
      (node (ref "U3") (pin "7") (pinfunction "SO_7") (pintype "output"))
    )
    (net (code "20") (name "/SPI1_SCK") (class "Default")
      (node (ref "R6") (pin "1") (pinfunction "1_1") (pintype "passive"))
      (node (ref "U3") (pin "5") (pinfunction "SCK_5") (pintype "input"))
      (node (ref "U4") (pin "5") (pinfunction "SCK_5") (pintype "input"))
    )
    (net (code "21") (name "/SPI1_SCK_R") (class "Default")
      (node (ref "R6") (pin "2") (pinfunction "2_2") (pintype "passive"))
      (node (ref "U1") (pin "15") (pinfunction "PA5_15") (pintype "bidirectional"))
    )
    (net (code "22") (name "/SPI2_CS_USB") (class "Default")
      (node (ref "R9") (pin "1") (pinfunction "1_1") (pintype "passive"))
      (node (ref "U2") (pin "5") (pinfunction "GP0_5") (pintype "bidirectional"))
    )
    (net (code "23") (name "/SPI2_CS_USB_R") (class "Default")
      (node (ref "R9") (pin "2") (pinfunction "2_2") (pintype "passive"))
      (node (ref "U1") (pin "25") (pinfunction "PB12_25") (pintype "bidirectional"))
    )
    (net (code "24") (name "/SPI2_MISO") (class "Default")
      (node (ref "R1") (pin "1") (pinfunction "1_1") (pintype "passive"))
      (node (ref "U1") (pin "27") (pinfunction "PB14_27") (pintype "bidirectional"))
    )
    (net (code "25") (name "/SPI2_MISO_R") (class "Default")
      (node (ref "R1") (pin "2") (pinfunction "2_2") (pintype "passive"))
      (node (ref "U2") (pin "13") (pinfunction "MISO_13") (pintype "input"))
    )
    (net (code "26") (name "/SPI2_MOSI") (class "Default")
      (node (ref "R12") (pin "1") (pinfunction "1_1") (pintype "passive"))
      (node (ref "U2") (pin "9") (pinfunction "MOSI_9") (pintype "output"))
    )
    (net (code "27") (name "/SPI2_MOSI_R") (class "Default")
      (node (ref "R12") (pin "2") (pinfunction "2_2") (pintype "passive"))
      (node (ref "U1") (pin "28") (pinfunction "PB15_28") (pintype "bidirectional"))
    )
    (net (code "28") (name "/SPI2_SCK") (class "Default")
      (node (ref "R10") (pin "1") (pinfunction "1_1") (pintype "passive"))
      (node (ref "U2") (pin "11") (pinfunction "SCK_11") (pintype "output"))
    )
    (net (code "29") (name "/SPI2_SCK_R") (class "Default")
      (node (ref "R10") (pin "2") (pinfunction "2_2") (pintype "passive"))
      (node (ref "U1") (pin "26") (pinfunction "PB13_26") (pintype "bidirectional"))
    )
    (net (code "30") (name "/SPI_ACK") (class "Default")
      (node (ref "U1") (pin "42") (pinfunction "PB6_42") (pintype "bidirectional"))
      (node (ref "U2") (pin "15") (pinfunction "GP7_15") (pintype "bidirectional"))
    )
    (net (code "31") (name "/SPI_REQ") (class "Default")
      (node (ref "U1") (pin "43") (pinfunction "PB7_43") (pintype "bidirectional"))
      (node (ref "U2") (pin "16") (pinfunction "GP8_16") (pintype "bidirectional"))
    )
    (net (code "32") (name "/SWD_CLK") (class "Default")
      (node (ref "P3") (pin "4") (pinfunction "4_4") (pintype "passive"))
      (node (ref "R7") (pin "2") (pinfunction "2_2") (pintype "passive"))
      (node (ref "U1") (pin "37") (pinfunction "PA14(SWCLK)_37") (pintype "bidirectional"))
    )
    (net (code "33") (name "/SWD_DIO") (class "Default")
      (node (ref "P3") (pin "2") (pinfunction "2_2") (pintype "passive"))
      (node (ref "R4") (pin "1") (pinfunction "1_1") (pintype "passive"))
      (node (ref "U1") (pin "34") (pinfunction "PA13(SWDIO)_34") (pintype "bidirectional"))
    )
    (net (code "34") (name "/T+") (class "Default")
      (node (ref "J3") (pin "4") (pinfunction "4_4") (pintype "passive"))
      (node (ref "L1") (pin "1") (pinfunction "1_1") (pintype "passive"))
    )
    (net (code "35") (name "/T-") (class "Default")
      (node (ref "J3") (pin "3") (pinfunction "3_3") (pintype "passive"))
      (node (ref "L2") (pin "1") (pinfunction "1_1") (pintype "passive"))
    )
    (net (code "36") (name "/UART_RX") (class "Default")
      (node (ref "P1") (pin "1") (pinfunction "1_1") (pintype "passive"))
      (node (ref "U1") (pin "31") (pinfunction "PA10_31") (pintype "bidirectional"))
    )
    (net (code "37") (name "/UART_TX") (class "Default")
      (node (ref "P1") (pin "2") (pinfunction "2_2") (pintype "passive"))
      (node (ref "U1") (pin "30") (pinfunction "PA9_30") (pintype "bidirectional"))
    )
    (net (code "38") (name "/USB_CONF") (class "Default")
      (node (ref "U1") (pin "40") (pinfunction "PB4_40") (pintype "bidirectional"))
      (node (ref "U2") (pin "12") (pinfunction "GP5_12") (pintype "bidirectional"))
    )
    (net (code "39") (name "/USB_LOWPWR") (class "Default")
      (node (ref "U1") (pin "39") (pinfunction "PB3_39") (pintype "bidirectional"))
      (node (ref "U2") (pin "10") (pinfunction "GP4_10") (pintype "bidirectional"))
    )
    (net (code "40") (name "/USB_N") (class "Default")
      (node (ref "P2") (pin "2") (pinfunction "2_2") (pintype "passive"))
      (node (ref "U2") (pin "18") (pinfunction "D-_18") (pintype "bidirectional"))
    )
    (net (code "41") (name "/USB_P") (class "Default")
      (node (ref "P2") (pin "3") (pinfunction "3_3") (pintype "passive"))
      (node (ref "U2") (pin "19") (pinfunction "D+_19") (pintype "bidirectional"))
    )
    (net (code "42") (name "/USB_SUSP") (class "Default")
      (node (ref "U1") (pin "20") (pinfunction "PB2_20") (pintype "bidirectional"))
      (node (ref "U2") (pin "7") (pinfunction "GP2_7") (pintype "bidirectional"))
    )
    (net (code "43") (name "/ZERO_DET") (class "Default")
      (node (ref "R16") (pin "2") (pinfunction "2_2") (pintype "passive"))
      (node (ref "U1") (pin "10") (pinfunction "PA0_10") (pintype "bidirectional"))
    )
    (net (code "44") (name "GND") (class "Default")
      (node (ref "C1") (pin "2") (pinfunction "2_2") (pintype "passive"))
      (node (ref "C10") (pin "2") (pinfunction "2_2") (pintype "passive"))
      (node (ref "C11") (pin "1") (pinfunction "C_1") (pintype "passive"))
      (node (ref "C12") (pin "2") (pinfunction "2_2") (pintype "passive"))
      (node (ref "C13") (pin "2") (pinfunction "2_2") (pintype "passive"))
      (node (ref "C14") (pin "1") (pinfunction "C_1") (pintype "passive"))
      (node (ref "C15") (pin "2") (pinfunction "2_2") (pintype "passive"))
      (node (ref "C16") (pin "1") (pinfunction "1_1") (pintype "passive"))
      (node (ref "C17") (pin "1") (pinfunction "1_1") (pintype "passive"))
      (node (ref "C18") (pin "2") (pinfunction "2_2") (pintype "passive"))
      (node (ref "C2") (pin "2") (pinfunction "2_2") (pintype "passive"))
      (node (ref "C20") (pin "2") (pinfunction "2_2") (pintype "passive"))
      (node (ref "C21") (pin "2") (pinfunction "2_2") (pintype "passive"))
      (node (ref "C23") (pin "2") (pinfunction "2_2") (pintype "passive"))
      (node (ref "C3") (pin "2") (pinfunction "2_2") (pintype "passive"))
      (node (ref "C4") (pin "2") (pinfunction "2_2") (pintype "passive"))
      (node (ref "C5") (pin "2") (pinfunction "2_2") (pintype "passive"))
      (node (ref "C6") (pin "2") (pinfunction "2_2") (pintype "passive"))
      (node (ref "C7") (pin "1") (pinfunction "1_1") (pintype "passive"))
      (node (ref "C8") (pin "1") (pinfunction "1_1") (pintype "passive"))
      (node (ref "C9") (pin "2") (pinfunction "2_2") (pintype "passive"))
      (node (ref "D1") (pin "2") (pinfunction "+_2") (pintype "passive"))
      (node (ref "D2") (pin "1") (pinfunction "C_1") (pintype "passive"))
      (node (ref "J5") (pin "2") (pinfunction "2_2") (pintype "passive"))
      (node (ref "J6") (pin "2") (pinfunction "2_2") (pintype "passive"))
      (node (ref "P2") (pin "4") (pinfunction "4_4") (pintype "passive"))
      (node (ref "P2") (pin "5") (pinfunction "5_5") (pintype "passive"))
      (node (ref "P3") (pin "3") (pinfunction "3_3") (pintype "passive"))
      (node (ref "P3") (pin "5") (pinfunction "5_5") (pintype "passive"))
      (node (ref "P3") (pin "7") (pinfunction "7_7") (pintype "passive"))
      (node (ref "P3") (pin "9") (pinfunction "9_9") (pintype "passive"))
      (node (ref "P4") (pin "4") (pinfunction "4_4") (pintype "passive"))
      (node (ref "P5") (pin "4") (pinfunction "4_4") (pintype "passive"))
      (node (ref "Q2") (pin "2") (pinfunction "C_2") (pintype "passive"))
      (node (ref "Q3") (pin "2") (pinfunction "C_2") (pintype "passive"))
      (node (ref "R13") (pin "2") (pinfunction "2_2") (pintype "passive"))
      (node (ref "R18") (pin "2") (pinfunction "2_2") (pintype "passive"))
      (node (ref "R24") (pin "1") (pinfunction "1_1") (pintype "passive"))
      (node (ref "R7") (pin "1") (pinfunction "1_1") (pintype "passive"))
      (node (ref "SW1") (pin "1") (pinfunction "1_1") (pintype "passive"))
      (node (ref "U1") (pin "23") (pinfunction "VSS_23") (pintype "power_in"))
      (node (ref "U1") (pin "47") (pinfunction "VSS_47") (pintype "power_in"))
      (node (ref "U1") (pin "8") (pinfunction "VSSA_8") (pintype "power_in"))
      (node (ref "U2") (pin "20") (pinfunction "VSS_20") (pintype "power_in"))
      (node (ref "U3") (pin "1") (pinfunction "GND_1") (pintype "power_in"))
      (node (ref "U4") (pin "1") (pinfunction "GND_1") (pintype "power_in"))
      (node (ref "VR1") (pin "1") (pinfunction "FIXED/ADJ_1") (pintype "input"))
    )
    (net (code "45") (name "Net-(C17-Pad2)") (class "Default")
      (node (ref "C17") (pin "2") (pinfunction "2_2") (pintype "passive"))
      (node (ref "R29") (pin "2") (pinfunction "2_2") (pintype "passive"))
      (node (ref "Y2") (pin "1") (pinfunction "1_1") (pintype "passive"))
    )
    (net (code "46") (name "Net-(D1-1_~)") (class "Default")
      (node (ref "D1") (pin "1") (pinfunction "1_~_1") (pintype "passive"))
      (node (ref "J1") (pin "1") (pinfunction "1_1") (pintype "passive"))
    )
    (net (code "47") (name "Net-(D1-2_~)") (class "Default")
      (node (ref "D1") (pin "4") (pinfunction "2_~_4") (pintype "passive"))
      (node (ref "J1") (pin "2") (pinfunction "2_2") (pintype "passive"))
    )
    (net (code "48") (name "Net-(D2-A)") (class "Default")
      (node (ref "D2") (pin "2") (pinfunction "A_2") (pintype "passive"))
      (node (ref "R8") (pin "1") (pinfunction "1_1") (pintype "passive"))
    )
    (net (code "49") (name "Net-(D3-G)") (class "Default")
      (node (ref "D3") (pin "3") (pinfunction "G_3") (pintype "passive"))
      (node (ref "Q3") (pin "4") (pinfunction "1_MAIN_TERM_4") (pintype "passive"))
    )
    (net (code "50") (name "Net-(D3-MT2)") (class "Default")
      (node (ref "D3") (pin "2") (pinfunction "MT2_2") (pintype "passive"))
      (node (ref "J3") (pin "1") (pinfunction "1_1") (pintype "passive"))
    )
    (net (code "51") (name "Net-(J4-Pad1)") (class "Default")
      (node (ref "J4") (pin "1") (pinfunction "1_1") (pintype "passive"))
      (node (ref "L4") (pin "1") (pinfunction "1_1") (pintype "passive"))
    )
    (net (code "52") (name "Net-(J4-Pad2)") (class "Default")
      (node (ref "J4") (pin "2") (pinfunction "2_2") (pintype "passive"))
      (node (ref "L3") (pin "1") (pinfunction "1_1") (pintype "passive"))
    )
    (net (code "53") (name "Net-(Q1-B)") (class "Default")
      (node (ref "Q1") (pin "1") (pinfunction "B_1") (pintype "passive"))
      (node (ref "R3") (pin "1") (pinfunction "1_1") (pintype "passive"))
    )
    (net (code "54") (name "Net-(Q1-E)") (class "Default")
      (node (ref "Q1") (pin "2") (pinfunction "E_2") (pintype "passive"))
      (node (ref "R8") (pin "2") (pinfunction "2_2") (pintype "passive"))
    )
    (net (code "55") (name "Net-(Q2-A)") (class "Default")
      (node (ref "Q2") (pin "1") (pinfunction "A_1") (pintype "passive"))
      (node (ref "R14") (pin "1") (pinfunction "1_1") (pintype "passive"))
    )
    (net (code "56") (name "Net-(Q2-E)") (class "Default")
      (node (ref "Q2") (pin "3") (pinfunction "E_3") (pintype "passive"))
      (node (ref "R16") (pin "1") (pinfunction "1_1") (pintype "passive"))
      (node (ref "R18") (pin "1") (pinfunction "1_1") (pintype "passive"))
    )
    (net (code "57") (name "Net-(Q3-2_MAIN_TERM)") (class "Default")
      (node (ref "Q3") (pin "6") (pinfunction "2_MAIN_TERM_6") (pintype "passive"))
      (node (ref "R20") (pin "2") (pinfunction "2_2") (pintype "passive"))
    )
    (net (code "58") (name "Net-(Q3-A)") (class "Default")
      (node (ref "Q3") (pin "1") (pinfunction "A_1") (pintype "passive"))
      (node (ref "R19") (pin "1") (pinfunction "1_1") (pintype "passive"))
    )
    (net (code "59") (name "Net-(Q4-B)") (class "Default")
      (node (ref "Q4") (pin "1") (pinfunction "B_1") (pintype "passive"))
      (node (ref "R26") (pin "1") (pinfunction "1_1") (pintype "passive"))
    )
    (net (code "60") (name "Net-(Q4-E)") (class "Default")
      (node (ref "Q4") (pin "2") (pinfunction "E_2") (pintype "passive"))
      (node (ref "Q5") (pin "1") (pinfunction "B_1") (pintype "passive"))
    )
    (net (code "61") (name "Net-(Q5-E)") (class "Default")
      (node (ref "J5") (pin "1") (pinfunction "1_1") (pintype "passive"))
      (node (ref "Q5") (pin "3") (pinfunction "E_3") (pintype "passive"))
    )
    (net (code "62") (name "Net-(Q6-B)") (class "Default")
      (node (ref "Q6") (pin "1") (pinfunction "B_1") (pintype "passive"))
      (node (ref "R27") (pin "1") (pinfunction "1_1") (pintype "passive"))
    )
    (net (code "63") (name "Net-(Q6-E)") (class "Default")
      (node (ref "Q6") (pin "2") (pinfunction "E_2") (pintype "passive"))
      (node (ref "Q7") (pin "1") (pinfunction "B_1") (pintype "passive"))
    )
    (net (code "64") (name "Net-(Q7-E)") (class "Default")
      (node (ref "J6") (pin "1") (pinfunction "1_1") (pintype "passive"))
      (node (ref "Q7") (pin "3") (pinfunction "E_3") (pintype "passive"))
    )
    (net (code "65") (name "Net-(U1A-BOOT0)") (class "Default")
      (node (ref "R13") (pin "1") (pinfunction "1_1") (pintype "passive"))
      (node (ref "U1") (pin "44") (pinfunction "BOOT0_44") (pintype "input"))
    )
    (net (code "66") (name "Net-(U1A-NRST)") (class "Default")
      (node (ref "C18") (pin "1") (pinfunction "1_1") (pintype "passive"))
      (node (ref "R15") (pin "1") (pinfunction "1_1") (pintype "passive"))
      (node (ref "R17") (pin "1") (pinfunction "1_1") (pintype "passive"))
      (node (ref "U1") (pin "7") (pinfunction "NRST_7") (pintype "bidirectional"))
    )
    (net (code "67") (name "Net-(U1A-PF0-OSC_IN(PF0))") (class "Default")
      (node (ref "C16") (pin "2") (pinfunction "2_2") (pintype "passive"))
      (node (ref "U1") (pin "5") (pinfunction "PF0-OSC_IN(PF0)_5") (pintype "bidirectional"))
      (node (ref "Y2") (pin "2") (pinfunction "2_2") (pintype "passive"))
    )
    (net (code "68") (name "Net-(U1A-PF1-OSC_OUT(PF1))") (class "Default")
      (node (ref "R29") (pin "1") (pinfunction "1_1") (pintype "passive"))
      (node (ref "U1") (pin "6") (pinfunction "PF1-OSC_OUT(PF1)_6") (pintype "bidirectional"))
    )
    (net (code "69") (name "Net-(U2-GP3)") (class "Default")
      (node (ref "R3") (pin "2") (pinfunction "2_2") (pintype "passive"))
      (node (ref "U2") (pin "8") (pinfunction "GP3_8") (pintype "bidirectional"))
    )
    (net (code "70") (name "Net-(U2-OSC1)") (class "Default")
      (node (ref "C7") (pin "2") (pinfunction "2_2") (pintype "passive"))
      (node (ref "U2") (pin "2") (pinfunction "OSC1_2") (pintype "input"))
      (node (ref "Y1") (pin "2") (pinfunction "2_2") (pintype "passive"))
    )
    (net (code "71") (name "Net-(U2-OSC2)") (class "Default")
      (node (ref "C8") (pin "2") (pinfunction "2_2") (pintype "passive"))
      (node (ref "U2") (pin "3") (pinfunction "OSC2_3") (pintype "output"))
      (node (ref "Y1") (pin "1") (pinfunction "1_1") (pintype "passive"))
    )
    (net (code "72") (name "Net-(U2-~{RST})") (class "Default")
      (node (ref "R2") (pin "2") (pinfunction "2_2") (pintype "passive"))
      (node (ref "U2") (pin "4") (pinfunction "~{RST}_4") (pintype "input"))
    )
    (net (code "73") (name "Net-(U3-T+)") (class "Default")
      (node (ref "C19") (pin "1") (pinfunction "1_1") (pintype "passive"))
      (node (ref "L1") (pin "2") (pinfunction "2_2") (pintype "passive"))
      (node (ref "U3") (pin "3") (pinfunction "T+_3") (pintype "input"))
    )
    (net (code "74") (name "Net-(U3-T-)") (class "Default")
      (node (ref "C19") (pin "2") (pinfunction "2_2") (pintype "passive"))
      (node (ref "L2") (pin "2") (pinfunction "2_2") (pintype "passive"))
      (node (ref "U3") (pin "2") (pinfunction "T-_2") (pintype "input"))
    )
    (net (code "75") (name "Net-(U4-T+)") (class "Default")
      (node (ref "C22") (pin "1") (pinfunction "1_1") (pintype "passive"))
      (node (ref "L3") (pin "2") (pinfunction "2_2") (pintype "passive"))
      (node (ref "U4") (pin "3") (pinfunction "T+_3") (pintype "input"))
    )
    (net (code "76") (name "Net-(U4-T-)") (class "Default")
      (node (ref "C22") (pin "2") (pinfunction "2_2") (pintype "passive"))
      (node (ref "L4") (pin "2") (pinfunction "2_2") (pintype "passive"))
      (node (ref "U4") (pin "2") (pinfunction "T-_2") (pintype "input"))
    )
    (net (code "77") (name "unconnected-(J1-Pad3)") (class "Default")
      (node (ref "J1") (pin "3") (pinfunction "3_3") (pintype "passive+no_connect"))
    )
    (net (code "78") (name "unconnected-(J1-Pad4)") (class "Default")
      (node (ref "J1") (pin "4") (pinfunction "4_4") (pintype "passive+no_connect"))
    )
    (net (code "79") (name "unconnected-(J1-Pad5)") (class "Default")
      (node (ref "J1") (pin "5") (pinfunction "5_5") (pintype "passive+no_connect"))
    )
    (net (code "80") (name "unconnected-(P2-Pad1)") (class "Default")
      (node (ref "P2") (pin "1") (pinfunction "1_1") (pintype "passive+no_connect"))
    )
    (net (code "81") (name "unconnected-(P3-Pad6)") (class "Default")
      (node (ref "P3") (pin "6") (pinfunction "6_6") (pintype "passive"))
    )
    (net (code "82") (name "unconnected-(P3-Pad8)") (class "Default")
      (node (ref "P3") (pin "8") (pinfunction "8_8") (pintype "passive"))
    )
    (net (code "83") (name "unconnected-(Q3-NC-Pad3)") (class "Default")
      (node (ref "Q3") (pin "3") (pinfunction "NC_3") (pintype "passive+no_connect"))
    )
    (net (code "84") (name "unconnected-(Q3-NC-Pad5)") (class "Default")
      (node (ref "Q3") (pin "5") (pinfunction "NC_5") (pintype "passive+no_connect"))
    )
    (net (code "85") (name "unconnected-(U1A-PA3-Pad13)") (class "Default")
      (node (ref "U1") (pin "13") (pinfunction "PA3_13") (pintype "bidirectional"))
    )
    (net (code "86") (name "unconnected-(U1A-PA7-Pad17)") (class "Default")
      (node (ref "U1") (pin "17") (pinfunction "PA7_17") (pintype "bidirectional"))
    )
    (net (code "87") (name "unconnected-(U1A-PA8-Pad29)") (class "Default")
      (node (ref "U1") (pin "29") (pinfunction "PA8_29") (pintype "bidirectional"))
    )
    (net (code "88") (name "unconnected-(U1A-PA11-Pad32)") (class "Default")
      (node (ref "U1") (pin "32") (pinfunction "PA11_32") (pintype "bidirectional"))
    )
    (net (code "89") (name "unconnected-(U1A-PA12-Pad33)") (class "Default")
      (node (ref "U1") (pin "33") (pinfunction "PA12_33") (pintype "bidirectional"))
    )
    (net (code "90") (name "unconnected-(U1A-PC13-Pad2)") (class "Default")
      (node (ref "U1") (pin "2") (pinfunction "PC13_2") (pintype "bidirectional"))
    )
    (net (code "91") (name "unconnected-(U1A-PC14-OSC32_IN(PC14)-Pad3)") (class "Default")
      (node (ref "U1") (pin "3") (pinfunction "PC14-OSC32_IN(PC14)_3") (pintype "bidirectional"))
    )
    (net (code "92") (name "unconnected-(U1A-PC15-OSC32_OUT(PC15)-Pad4)") (class "Default")
      (node (ref "U1") (pin "4") (pinfunction "PC15-OSC32_OUT(PC15)_4") (pintype "bidirectional"))
    )
    (net (code "93") (name "unconnected-(U1A-PF6-Pad35)") (class "Default")
      (node (ref "U1") (pin "35") (pinfunction "PF6_35") (pintype "bidirectional"))
    )
    (net (code "94") (name "unconnected-(U1A-PF7-Pad36)") (class "Default")
      (node (ref "U1") (pin "36") (pinfunction "PF7_36") (pintype "bidirectional"))
    )
    (net (code "95") (name "unconnected-(U2-GP1-Pad6)") (class "Default")
      (node (ref "U2") (pin "6") (pinfunction "GP1_6") (pintype "bidirectional"))
    )
    (net (code "96") (name "unconnected-(U3-DNC-Pad8)") (class "Default")
      (node (ref "U3") (pin "8") (pinfunction "DNC_8") (pintype "passive"))
    )
    (net (code "97") (name "unconnected-(U4-DNC-Pad8)") (class "Default")
      (node (ref "U4") (pin "8") (pinfunction "DNC_8") (pintype "passive"))
    )
    (net (code "98") (name "~230") (class "Default")
      (node (ref "D3") (pin "1") (pinfunction "MT1_1") (pintype "passive"))
      (node (ref "J2") (pin "1") (pinfunction "1_1") (pintype "passive"))
      (node (ref "J2") (pin "2") (pinfunction "2_2") (pintype "passive"))
      (node (ref "R20") (pin "1") (pinfunction "1_1") (pintype "passive"))
      (node (ref "R28") (pin "2") (pinfunction "2_2") (pintype "passive"))
    )
    (net (code "99") (name "~N") (class "Default")
      (node (ref "J2") (pin "3") (pinfunction "3_3") (pintype "passive"))
      (node (ref "J2") (pin "4") (pinfunction "4_4") (pintype "passive"))
      (node (ref "J3") (pin "2") (pinfunction "2_2") (pintype "passive"))
      (node (ref "R28") (pin "1") (pinfunction "1_1") (pintype "passive"))
    )
  )
)
